# PWR_P3V3A.net
KiCad netlist of a schematic drawn in Altium Designer
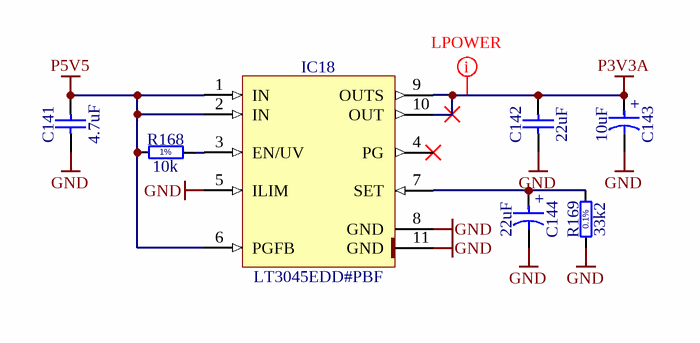
[diagram p0: PWR_P3V3A.SchDoc]

(export (version "E")
  (design (tool "Eeschema 10.0.6"))
  (components
    (comp (ref "C141")
      (value "4.7uF")
      (footprint "CAPC1709X95N")
      (description "Non-polarised capacitor")
      (fields
        (field (name "PART NUMBER") "CC0603_4.7UF_16V_10%_X5R")
        (field (name "VOLTAGE") "16V")
        (field (name "AUTHOR") "CERN DEM JLC")
      )
      (libsource (lib "Capacitors") (part "Capacitor - non polarized"))
    )
    (comp (ref "C142")
      (value "22uF")
      (footprint "CAPC2012X135N")
      (description "Non-polarised capacitor")
      (fields
        (field (name "PART NUMBER") "CC0805_22UF_16V_10%_X5R")
        (field (name "VOLTAGE") "16V")
        (field (name "AUTHOR") "CERN DEM JLC")
      )
      (libsource (lib "Capacitors") (part "Capacitor - non polarized"))
    )
    (comp (ref "C143")
      (value "10uF")
      (footprint "CAPMP3216X180N")
      (description "Polarised capacitor")
      (fields
        (field (name "PART NUMBER") "CTE3216-18_10UF_16V_20%_AVX_TCJ")
        (field (name "VOLTAGE") "16V")
        (field (name "AUTHOR") "CERN DEM JLC")
      )
      (libsource (lib "Capacitors") (part "Capacitor - polarized"))
    )
    (comp (ref "C144")
      (value "22uF")
      (footprint "CAPMP3216X180N")
      (description "Polarised capacitor")
      (fields
        (field (name "PART NUMBER") "CTE3216-18_22UF_10V_10%")
        (field (name "VOLTAGE") "10V")
        (field (name "AUTHOR") "CERN DEM JLC")
      )
      (libsource (lib "Capacitors") (part "Capacitor - polarized"))
    )
    (comp (ref "IC18")
      (value "LT3045EDD#PBF")
      (footprint "SON50P300X300X80-11N-R175X248")
      (description "20V, 500mA, Ultralow Noise, Ultrahigh PSRR Linear Regulator")
      (fields (field (name "MANUFACTURER") "LINEAR TECHNOLOGY") (field (name "AUTHOR") "CERN DEM JLC"))
      (libsource (lib "ICs And Semiconductors") (part "LT3045EDD"))
    )
    (comp (ref "R168")
      (value "10k")
      (footprint "RESC1005X40N")
      (description "Resistor - 1%")
      (fields
        (field (name "PART NUMBER") "R0402_10K_1%_0.0625W_100PPM")
        (field (name "POWER") "0.0625W")
        (field (name "AUTHOR") "CERN DEM JLC")
      )
      (libsource (lib "Resistors") (part "Resistor - 1%"))
    )
    (comp (ref "R169")
      (value "33k2")
      (footprint "RESC1608X55N")
      (description "Resistor - 0.1%")
      (fields
        (field (name "PART NUMBER") "R0603_33K2_0.1%_0.063W_10PPM")
        (field (name "POWER") "0.063W")
        (field (name "AUTHOR") "CERN DEM JLC")
      )
      (libsource (lib "Resistors") (part "Resistor - 0.1%"))
    )
  )
  (nets
    (net (code "1") (name "GND") (class "Default")
      (node (ref "C141") (pin "1") (pinfunction "1_1") (pintype "passive"))
      (node (ref "C142") (pin "1") (pinfunction "1_1") (pintype "passive"))
      (node (ref "C143") (pin "2") (pinfunction "2_2") (pintype "passive"))
      (node (ref "C144") (pin "2") (pinfunction "2_2") (pintype "passive"))
      (node (ref "IC18") (pin "11") (pinfunction "GND_11") (pintype "power_in"))
      (node (ref "IC18") (pin "5") (pinfunction "ILIM_5") (pintype "input"))
      (node (ref "IC18") (pin "8") (pinfunction "GND_8") (pintype "power_in"))
      (node (ref "R169") (pin "1") (pinfunction "1_1") (pintype "passive"))
    )
    (net (code "2") (name "Net-(IC18-EN{slash}UV)") (class "Default")
      (node (ref "IC18") (pin "3") (pinfunction "EN/UV_3") (pintype "input"))
      (node (ref "R168") (pin "2") (pinfunction "2_2") (pintype "passive"))
    )
    (net (code "3") (name "Net-(IC18-SET)") (class "Default")
      (node (ref "C144") (pin "1") (pinfunction "1_1") (pintype "passive"))
      (node (ref "IC18") (pin "7") (pinfunction "SET_7") (pintype "input"))
      (node (ref "R169") (pin "2") (pinfunction "2_2") (pintype "passive"))
    )
    (net (code "4") (name "P3V3A") (class "Default")
      (node (ref "C142") (pin "2") (pinfunction "2_2") (pintype "passive"))
      (node (ref "C143") (pin "1") (pinfunction "1_1") (pintype "passive"))
      (node (ref "IC18") (pin "10") (pinfunction "OUT_10") (pintype "output"))
      (node (ref "IC18") (pin "9") (pinfunction "OUTS_9") (pintype "output"))
    )
    (net (code "5") (name "P5V5") (class "Default")
      (node (ref "C141") (pin "2") (pinfunction "2_2") (pintype "passive"))
      (node (ref "IC18") (pin "1") (pinfunction "IN_1") (pintype "input"))
      (node (ref "IC18") (pin "2") (pinfunction "IN_2") (pintype "input"))
      (node (ref "IC18") (pin "6") (pinfunction "PGFB_6") (pintype "input"))
      (node (ref "R168") (pin "1") (pinfunction "1_1") (pintype "passive"))
    )
    (net (code "6") (name "unconnected-(IC18-PG-Pad4)") (class "Default")
      (node (ref "IC18") (pin "4") (pinfunction "PG_4") (pintype "output+no_connect"))
    )
  )
)
